# TOF_Sensor_Unit.net
KiCad netlist of a schematic drawn in EasyEDA Pro
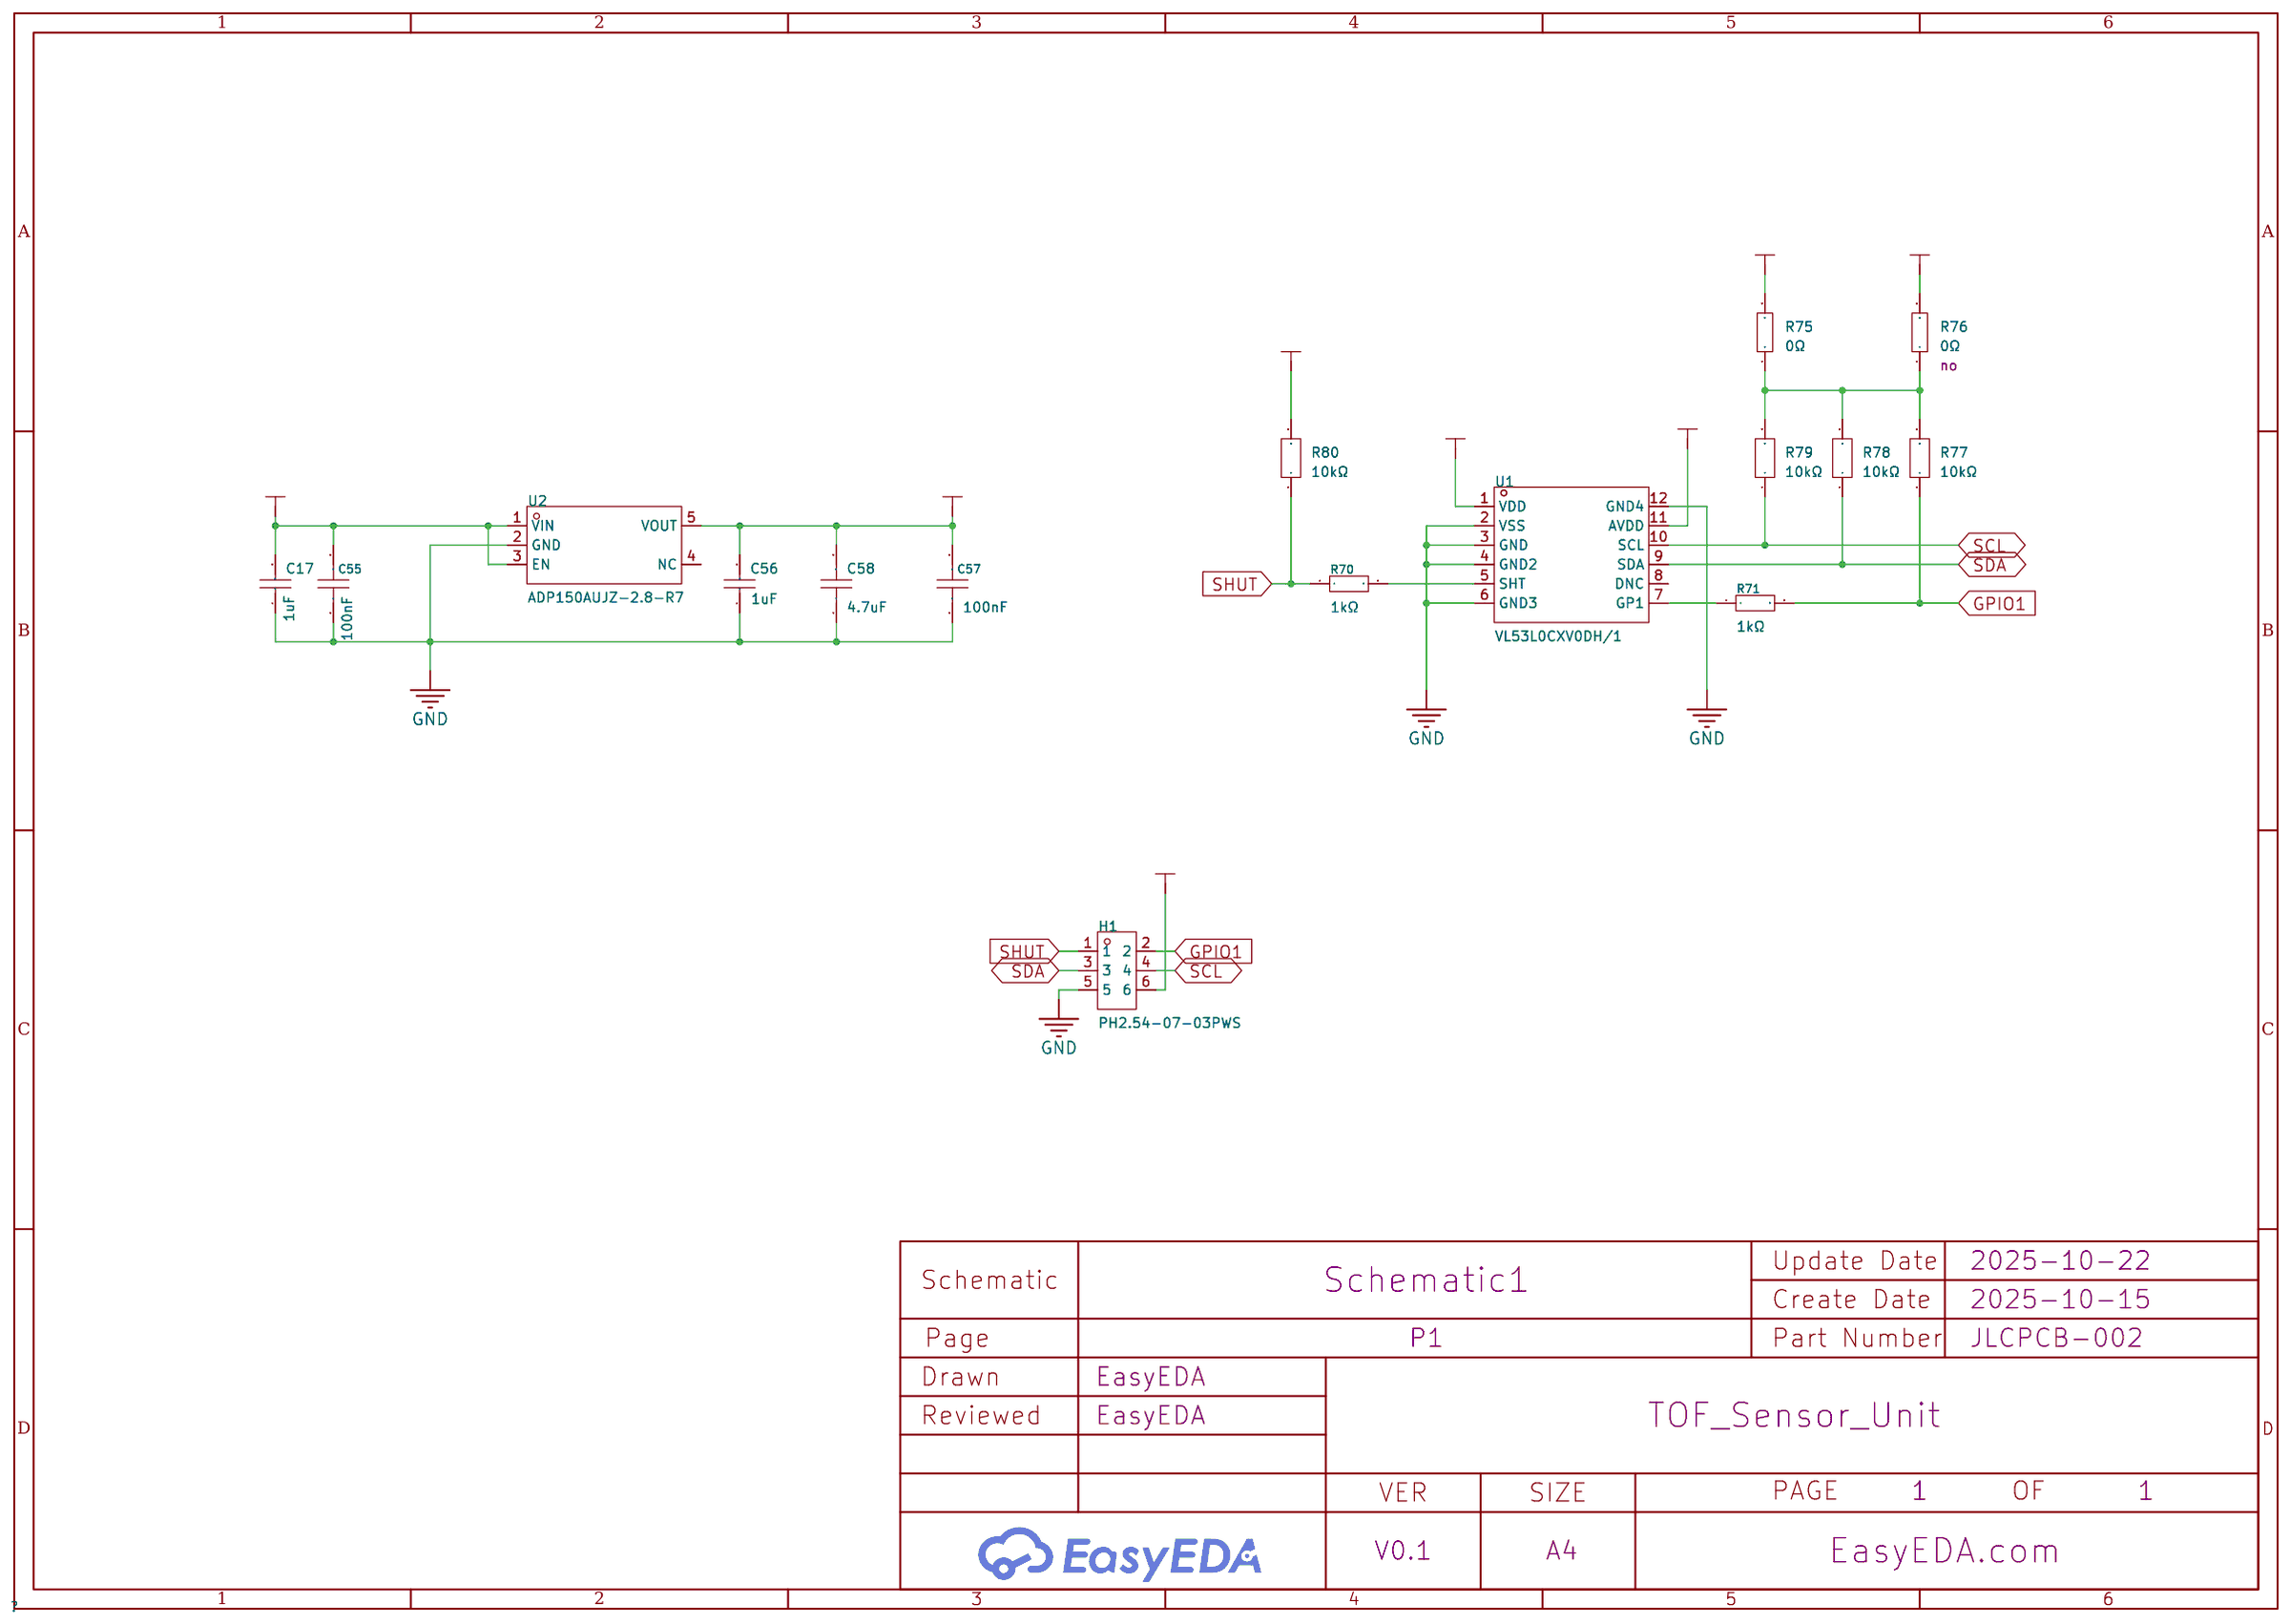
[diagram p0: schematic sheet]

(export (version "E")
  (design (tool "Eeschema 10.0.6"))
  (components
    (comp (ref "C17")
      (value "1uF")
      (footprint "easyedapro:C0603")
      (fields
        (field (name "Manufacturer Part") "CL10A105KO8NNNC")
        (field (name "Manufacturer") "SAMSUNG(三星)")
      )
      (libsource (lib "easyedapro") (part "CL10A105KO8NNNC"))
    )
    (comp (ref "C55")
      (value "100nF")
      (footprint "easyedapro:C0603")
      (fields
        (field (name "Manufacturer Part") "CC0603KRX7R6BB104")
        (field (name "Manufacturer") "YAGEO(国巨)")
      )
      (libsource (lib "easyedapro") (part "CC0603KRX7R6BB104"))
    )
    (comp (ref "C56")
      (value "1uF")
      (footprint "easyedapro:C0603")
      (fields
        (field (name "Manufacturer Part") "CL10A105KO8NNNC")
        (field (name "Manufacturer") "SAMSUNG(三星)")
      )
      (libsource (lib "easyedapro") (part "CL10A105KO8NNNC"))
    )
    (comp (ref "C57")
      (value "100nF")
      (footprint "easyedapro:C0603")
      (fields
        (field (name "Manufacturer Part") "CC0603KRX7R6BB104")
        (field (name "Manufacturer") "YAGEO(国巨)")
      )
      (libsource (lib "easyedapro") (part "CC0603KRX7R6BB104"))
    )
    (comp (ref "C58")
      (value "4.7uF")
      (footprint "easyedapro:C0603")
      (description "Capacitance:4.7uF Tolerance:±10% Tolerance:±10% Voltage Rating:25V Temperature Coefficient:X5R")
      (fields
        (field (name "Manufacturer Part") "CGA0603X5R475K250JT")
        (field (name "Manufacturer") "HRE(芯声)")
      )
      (libsource (lib "easyedapro") (part "CGA0603X5R475K250JT"))
    )
    (comp (ref "H1")
      (value "PH2.54-07-03PWS")
      (footprint "easyedapro:HDR-TH_6P-P2.54-H-M-R2-C3-S2.54-W12.3-N")
      (fields (field (name "Manufacturer") "XUNPU(讯普)"))
      (libsource (lib "easyedapro") (part "PH2.54-07-03PWS"))
    )
    (comp (ref "R70")
      (value "1kΩ")
      (footprint "easyedapro:R0603")
      (fields
        (field (name "Manufacturer Part") "0603WAF1001T5E")
        (field (name "Manufacturer") "UNI-ROYAL(厚声)")
      )
      (libsource (lib "easyedapro") (part "0603WAF1001T5E"))
    )
    (comp (ref "R71")
      (value "1kΩ")
      (footprint "easyedapro:R0603")
      (fields
        (field (name "Manufacturer Part") "0603WAF1001T5E")
        (field (name "Manufacturer") "UNI-ROYAL(厚声)")
      )
      (libsource (lib "easyedapro") (part "0603WAF1001T5E"))
    )
    (comp (ref "R75")
      (value "0Ω")
      (footprint "easyedapro:R0603")
      (fields
        (field (name "Manufacturer Part") "0603WAF0000T5E")
        (field (name "Manufacturer") "UNI-ROYAL(厚声)")
      )
      (libsource (lib "easyedapro") (part "0603WAF0000T5E"))
    )
    (comp (ref "R76")
      (value "0Ω")
      (footprint "easyedapro:R0603")
      (fields
        (field (name "Manufacturer Part") "0603WAF0000T5E")
        (field (name "Manufacturer") "UNI-ROYAL(厚声)")
        (field (name "Add into BOM") "no")
      )
      (libsource (lib "easyedapro") (part "0603WAF0000T5E"))
    )
    (comp (ref "R77")
      (value "10kΩ")
      (footprint "easyedapro:R0603")
      (fields (field (name "Manufacturer Part") "FRC0603J103 TS") (field (name "Manufacturer") "FOJAN(富捷)"))
      (libsource (lib "easyedapro") (part "FRC0603J103TS"))
    )
    (comp (ref "R78")
      (value "10kΩ")
      (footprint "easyedapro:R0603")
      (fields (field (name "Manufacturer Part") "FRC0603J103 TS") (field (name "Manufacturer") "FOJAN(富捷)"))
      (libsource (lib "easyedapro") (part "FRC0603J103TS"))
    )
    (comp (ref "R79")
      (value "10kΩ")
      (footprint "easyedapro:R0603")
      (fields (field (name "Manufacturer Part") "FRC0603J103 TS") (field (name "Manufacturer") "FOJAN(富捷)"))
      (libsource (lib "easyedapro") (part "FRC0603J103TS"))
    )
    (comp (ref "R80")
      (value "10kΩ")
      (footprint "easyedapro:R0603")
      (fields (field (name "Manufacturer Part") "FRC0603J103 TS") (field (name "Manufacturer") "FOJAN(富捷)"))
      (libsource (lib "easyedapro") (part "FRC0603J103TS"))
    )
    (comp (ref "U1")
      (value "VL53L0CXV0DH/1")
      (footprint "easyedapro:OPTO-SMD_12P_VL53L0CXV0DH-1")
      (description "Linear Range:200cm Linear Range:200cm")
      (fields (field (name "Manufacturer") "ST(意法半导体)"))
      (libsource (lib "easyedapro") (part "VL53L0CXV0DH/1"))
    )
    (comp (ref "U2")
      (value "ADP150AUJZ-2.8-R7")
      (footprint "easyedapro:TSOT-23-5_L2.9-W1.6-P0.95-LS2.8-BL")
      (fields (field (name "Manufacturer") "ADI(亚德诺)"))
      (libsource (lib "easyedapro") (part "ADP150AUJZ-2.8-R7"))
    )
  )
  (nets
    (net (code "1") (name "2V8") (class "Default")
      (node (ref "C56") (pin "2") (pinfunction "2_2") (pintype "input"))
      (node (ref "C57") (pin "2") (pinfunction "2_2") (pintype "input"))
      (node (ref "C58") (pin "2") (pinfunction "2_2") (pintype "unspecified"))
      (node (ref "R76") (pin "2") (pinfunction "2_2") (pintype "input"))
      (node (ref "R80") (pin "2") (pinfunction "2_2") (pintype "unspecified"))
      (node (ref "U1") (pin "1") (pinfunction "VDD_1") (pintype "unspecified"))
      (node (ref "U1") (pin "11") (pinfunction "AVDD_11") (pintype "unspecified"))
      (node (ref "U2") (pin "5") (pinfunction "VOUT_5") (pintype "unspecified"))
    )
    (net (code "2") (name "3V3") (class "Default")
      (node (ref "C17") (pin "2") (pinfunction "2_2") (pintype "input"))
      (node (ref "C55") (pin "2") (pinfunction "2_2") (pintype "input"))
      (node (ref "H1") (pin "6") (pinfunction "6_6") (pintype "unspecified"))
      (node (ref "R75") (pin "2") (pinfunction "2_2") (pintype "input"))
      (node (ref "U2") (pin "1") (pinfunction "VIN_1") (pintype "unspecified"))
      (node (ref "U2") (pin "3") (pinfunction "EN_3") (pintype "unspecified"))
    )
    (net (code "3") (name "GND") (class "Default")
      (node (ref "C17") (pin "1") (pinfunction "1_1") (pintype "input"))
      (node (ref "C55") (pin "1") (pinfunction "1_1") (pintype "input"))
      (node (ref "C56") (pin "1") (pinfunction "1_1") (pintype "input"))
      (node (ref "C57") (pin "1") (pinfunction "1_1") (pintype "input"))
      (node (ref "C58") (pin "1") (pinfunction "1_1") (pintype "unspecified"))
      (node (ref "H1") (pin "5") (pinfunction "5_5") (pintype "unspecified"))
      (node (ref "U1") (pin "12") (pinfunction "GND4_12") (pintype "unspecified"))
      (node (ref "U1") (pin "2") (pinfunction "VSS_2") (pintype "unspecified"))
      (node (ref "U1") (pin "3") (pinfunction "GND_3") (pintype "unspecified"))
      (node (ref "U1") (pin "4") (pinfunction "GND2_4") (pintype "unspecified"))
      (node (ref "U1") (pin "6") (pinfunction "GND3_6") (pintype "unspecified"))
      (node (ref "U2") (pin "2") (pinfunction "GND_2") (pintype "unspecified"))
    )
    (net (code "4") (name "GPIO1") (class "Default")
      (node (ref "H1") (pin "2") (pinfunction "2_2") (pintype "unspecified"))
      (node (ref "R71") (pin "2") (pinfunction "2_2") (pintype "input"))
      (node (ref "R77") (pin "1") (pinfunction "1_1") (pintype "unspecified"))
    )
    (net (code "5") (name "Net-(R75-Pad1)") (class "Default")
      (node (ref "R75") (pin "1") (pinfunction "1_1") (pintype "input"))
      (node (ref "R76") (pin "1") (pinfunction "1_1") (pintype "input"))
      (node (ref "R77") (pin "2") (pinfunction "2_2") (pintype "unspecified"))
      (node (ref "R78") (pin "2") (pinfunction "2_2") (pintype "unspecified"))
      (node (ref "R79") (pin "2") (pinfunction "2_2") (pintype "unspecified"))
    )
    (net (code "6") (name "Net-(U1-GP1)") (class "Default")
      (node (ref "R71") (pin "1") (pinfunction "1_1") (pintype "input"))
      (node (ref "U1") (pin "7") (pinfunction "GP1_7") (pintype "unspecified"))
    )
    (net (code "7") (name "Net-(U1-SHT)") (class "Default")
      (node (ref "R70") (pin "2") (pinfunction "2_2") (pintype "input"))
      (node (ref "U1") (pin "5") (pinfunction "SHT_5") (pintype "unspecified"))
    )
    (net (code "8") (name "SCL") (class "Default")
      (node (ref "H1") (pin "4") (pinfunction "4_4") (pintype "unspecified"))
      (node (ref "R79") (pin "1") (pinfunction "1_1") (pintype "unspecified"))
      (node (ref "U1") (pin "10") (pinfunction "SCL_10") (pintype "unspecified"))
    )
    (net (code "9") (name "SDA") (class "Default")
      (node (ref "H1") (pin "3") (pinfunction "3_3") (pintype "unspecified"))
      (node (ref "R78") (pin "1") (pinfunction "1_1") (pintype "unspecified"))
      (node (ref "U1") (pin "9") (pinfunction "SDA_9") (pintype "unspecified"))
    )
    (net (code "10") (name "SHUT") (class "Default")
      (node (ref "H1") (pin "1") (pinfunction "1_1") (pintype "unspecified"))
      (node (ref "R70") (pin "1") (pinfunction "1_1") (pintype "input"))
      (node (ref "R80") (pin "1") (pinfunction "1_1") (pintype "unspecified"))
    )
    (net (code "11") (name "unconnected-(U1-DNC-Pad8)") (class "Default")
      (node (ref "U1") (pin "8") (pinfunction "DNC_8") (pintype "unspecified"))
    )
    (net (code "12") (name "unconnected-(U2-NC-Pad4)") (class "Default")
      (node (ref "U2") (pin "4") (pinfunction "NC_4") (pintype "unspecified"))
    )
  )
)
